# senseBox-BMP280_v20.net
KiCad netlist of a schematic drawn in EAGLE
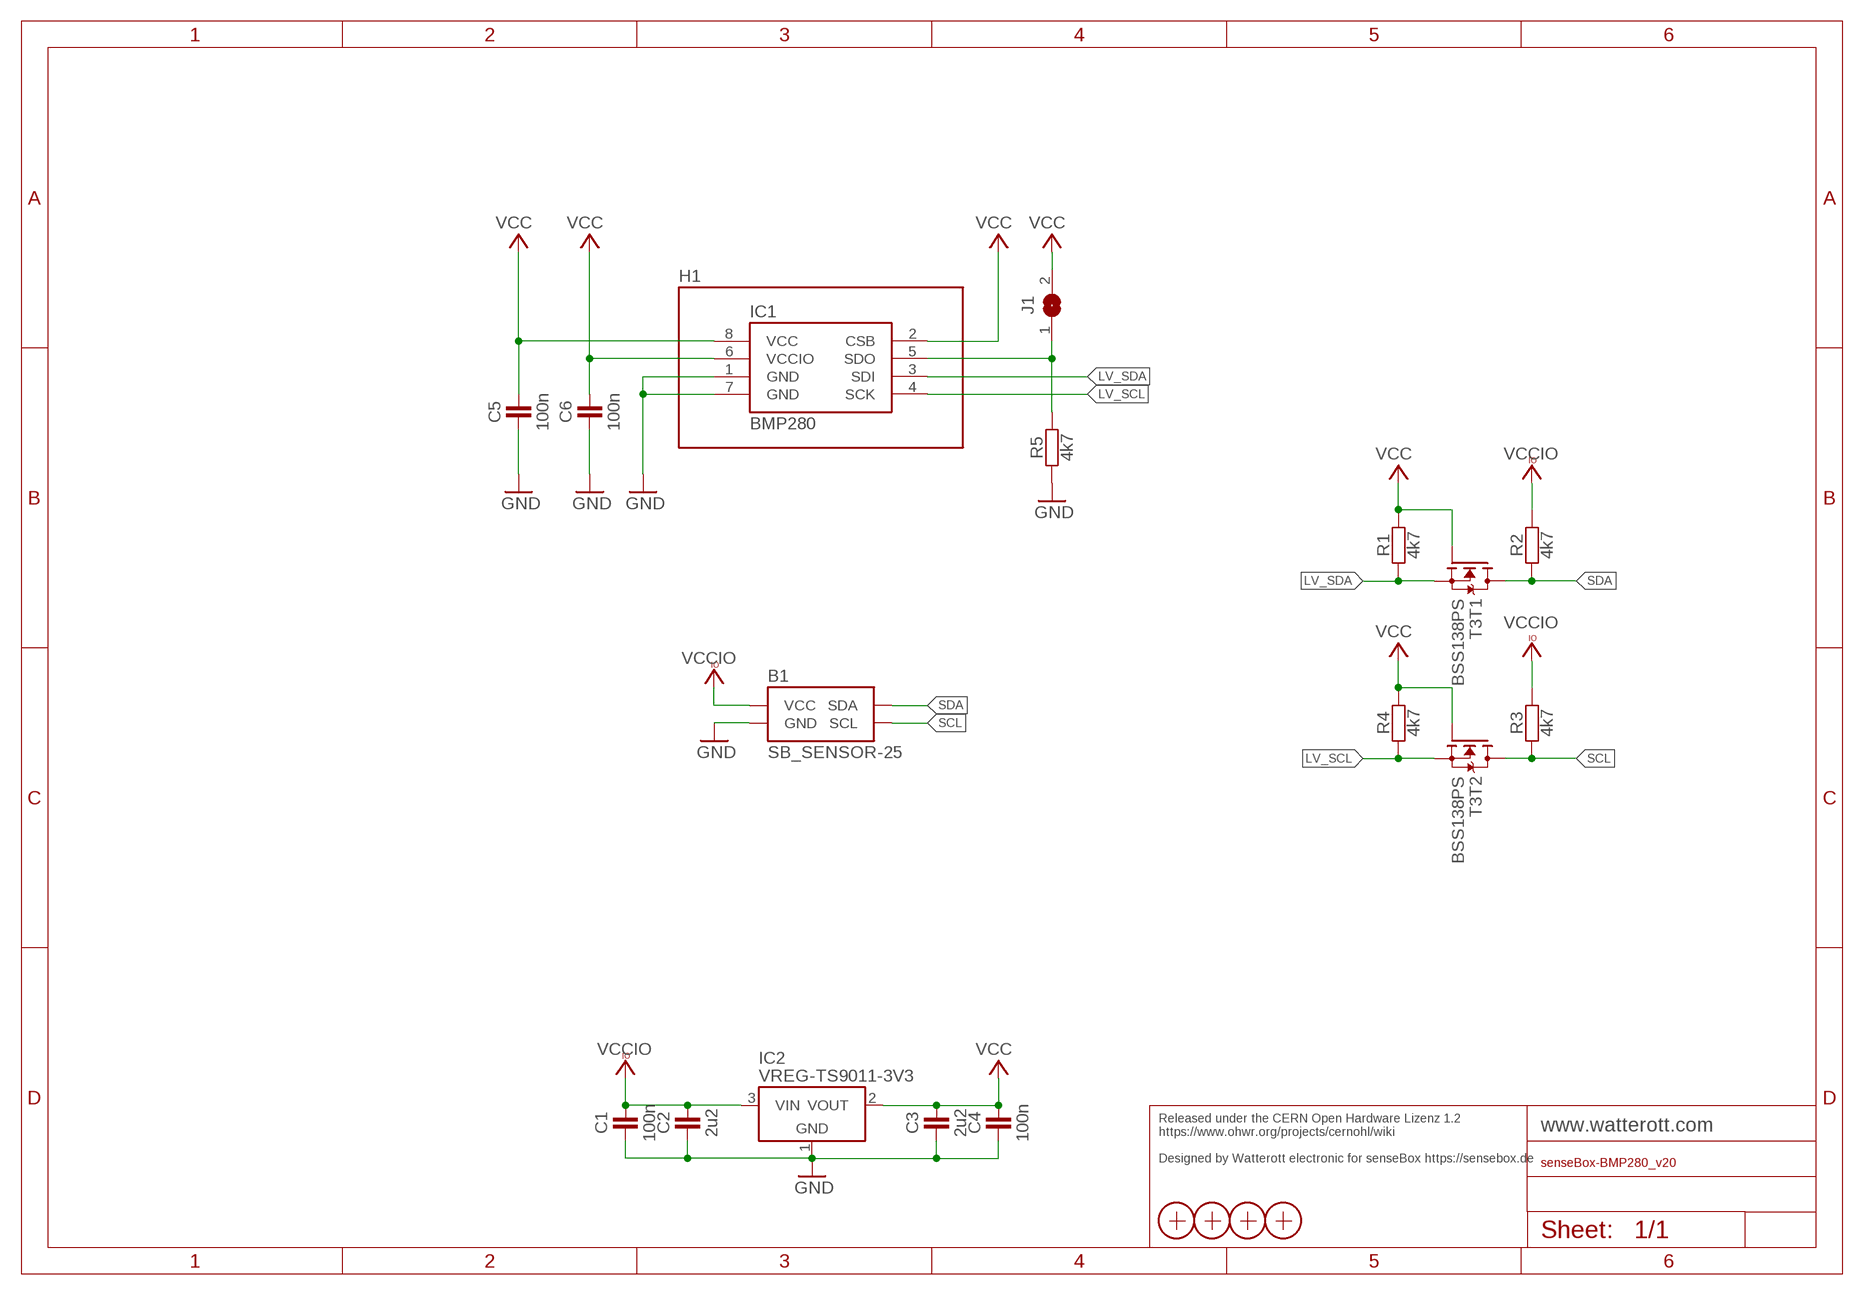
[diagram p0: schematic, sheet 1]

(export (version "E")
  (design (tool "Eeschema 10.0.6"))
  (components
    (comp (ref "B1")
      (value "SB_SENSOR-25")
      (footprint "eagle-import:SB-25X25")
      (libsource (lib "eagle-import") (part "SB_SENSOR-25"))
    )
    (comp (ref "C1")
      (value "100n")
      (footprint "eagle-import:C0402")
      (libsource (lib "eagle-import") (part "CAPACITOR-0402"))
    )
    (comp (ref "C2")
      (value "2u2")
      (footprint "eagle-import:C0402")
      (libsource (lib "eagle-import") (part "CAPACITOR-0402"))
    )
    (comp (ref "C3")
      (value "2u2")
      (footprint "eagle-import:C0402")
      (libsource (lib "eagle-import") (part "CAPACITOR-0402"))
    )
    (comp (ref "C4")
      (value "100n")
      (footprint "eagle-import:C0402")
      (libsource (lib "eagle-import") (part "CAPACITOR-0402"))
    )
    (comp (ref "C5")
      (value "100n")
      (footprint "eagle-import:C0402")
      (libsource (lib "eagle-import") (part "CAPACITOR-0402"))
    )
    (comp (ref "C6")
      (value "100n")
      (footprint "eagle-import:C0402")
      (libsource (lib "eagle-import") (part "CAPACITOR-0402"))
    )
    (comp (ref "H1")
      (value "SF2")
      (footprint "eagle-import:SF2")
      (libsource (lib "eagle-import") (part "SF2"))
    )
    (comp (ref "IC1")
      (value "BMP280")
      (footprint "eagle-import:LGA8")
      (libsource (lib "eagle-import") (part "BMP280"))
    )
    (comp (ref "IC2")
      (value "VREG-TS9011-3V3")
      (footprint "eagle-import:SOT23")
      (libsource (lib "eagle-import") (part "VREG-TS9011-3V3"))
    )
    (comp (ref "J1")
      (value "JUMPER2-0402-NC")
      (footprint "eagle-import:JUMPER2-0402_NC")
      (libsource (lib "eagle-import") (part "JUMPER2-0402-NC"))
    )
    (comp (ref "R1")
      (value "4k7")
      (footprint "eagle-import:C0402")
      (libsource (lib "eagle-import") (part "RESISTOR-0402"))
    )
    (comp (ref "R2")
      (value "4k7")
      (footprint "eagle-import:C0402")
      (libsource (lib "eagle-import") (part "RESISTOR-0402"))
    )
    (comp (ref "R3")
      (value "4k7")
      (footprint "eagle-import:C0402")
      (libsource (lib "eagle-import") (part "RESISTOR-0402"))
    )
    (comp (ref "R4")
      (value "4k7")
      (footprint "eagle-import:C0402")
      (libsource (lib "eagle-import") (part "RESISTOR-0402"))
    )
    (comp (ref "R5")
      (value "4k7")
      (footprint "eagle-import:C0402")
      (libsource (lib "eagle-import") (part "RESISTOR-0402"))
    )
    (comp (ref "T3")
      (value "BSS138PS")
      (footprint "eagle-import:SOT363")
      (libsource (lib "eagle-import") (part "BSS138PS"))
    )
    (comp (ref "X1")
      (value "PASSER-07")
      (footprint "eagle-import:PASSER_07MM")
      (libsource (lib "eagle-import") (part "PASSER-07"))
    )
    (comp (ref "X2")
      (value "PASSER-07")
      (footprint "eagle-import:PASSER_07MM")
      (libsource (lib "eagle-import") (part "PASSER-07"))
    )
    (comp (ref "X3")
      (value "PASSER-07")
      (footprint "eagle-import:PASSER_07MM")
      (libsource (lib "eagle-import") (part "PASSER-07"))
    )
    (comp (ref "X4")
      (value "PASSER-07")
      (footprint "eagle-import:PASSER_07MM")
      (libsource (lib "eagle-import") (part "PASSER-07"))
    )
  )
  (nets
    (net (code "1") (name "GND") (class "Default")
      (node (ref "B1") (pin "GND") (pinfunction "GND_GND") (pintype "power_in"))
      (node (ref "C1") (pin "1") (pinfunction "1_1") (pintype "passive"))
      (node (ref "C2") (pin "1") (pinfunction "1_1") (pintype "passive"))
      (node (ref "C3") (pin "1") (pinfunction "1_1") (pintype "passive"))
      (node (ref "C4") (pin "1") (pinfunction "1_1") (pintype "passive"))
      (node (ref "C5") (pin "1") (pinfunction "1_1") (pintype "passive"))
      (node (ref "C6") (pin "1") (pinfunction "1_1") (pintype "passive"))
      (node (ref "IC1") (pin "1") (pinfunction "GND_1") (pintype "power_in"))
      (node (ref "IC1") (pin "7") (pinfunction "GND_7") (pintype "power_in"))
      (node (ref "IC2") (pin "1") (pinfunction "GND_1") (pintype "power_in"))
      (node (ref "R5") (pin "1") (pinfunction "1_1") (pintype "passive"))
    )
    (net (code "2") (name "LV_SCL") (class "Default")
      (node (ref "IC1") (pin "4") (pinfunction "SCK_4") (pintype "bidirectional"))
      (node (ref "R4") (pin "1") (pinfunction "1_1") (pintype "passive"))
      (node (ref "T3") (pin "4") (pinfunction "S_4") (pintype "passive"))
    )
    (net (code "3") (name "LV_SDA") (class "Default")
      (node (ref "IC1") (pin "3") (pinfunction "SDI_3") (pintype "bidirectional"))
      (node (ref "R1") (pin "1") (pinfunction "1_1") (pintype "passive"))
      (node (ref "T3") (pin "1") (pinfunction "S_1") (pintype "passive"))
    )
    (net (code "4") (name "Net-(IC1-SDO)") (class "Default")
      (node (ref "IC1") (pin "5") (pinfunction "SDO_5") (pintype "bidirectional"))
      (node (ref "J1") (pin "1") (pinfunction "1_1") (pintype "passive"))
      (node (ref "R5") (pin "2") (pinfunction "2_2") (pintype "passive"))
    )
    (net (code "5") (name "SCL") (class "Default")
      (node (ref "B1") (pin "SCL") (pinfunction "SCL_SCL") (pintype "bidirectional"))
      (node (ref "R3") (pin "1") (pinfunction "1_1") (pintype "passive"))
      (node (ref "T3") (pin "3") (pinfunction "D_3") (pintype "passive"))
    )
    (net (code "6") (name "SDA") (class "Default")
      (node (ref "B1") (pin "SDA") (pinfunction "SDA_SDA") (pintype "bidirectional"))
      (node (ref "R2") (pin "1") (pinfunction "1_1") (pintype "passive"))
      (node (ref "T3") (pin "6") (pinfunction "D_6") (pintype "passive"))
    )
    (net (code "7") (name "VCC") (class "Default")
      (node (ref "C3") (pin "2") (pinfunction "2_2") (pintype "passive"))
      (node (ref "C4") (pin "2") (pinfunction "2_2") (pintype "passive"))
      (node (ref "C5") (pin "2") (pinfunction "2_2") (pintype "passive"))
      (node (ref "C6") (pin "2") (pinfunction "2_2") (pintype "passive"))
      (node (ref "IC1") (pin "2") (pinfunction "CSB_2") (pintype "input"))
      (node (ref "IC1") (pin "6") (pinfunction "VCCIO_6") (pintype "power_in"))
      (node (ref "IC1") (pin "8") (pinfunction "VCC_8") (pintype "power_in"))
      (node (ref "IC2") (pin "2") (pinfunction "VOUT_2") (pintype "power_in"))
      (node (ref "J1") (pin "2") (pinfunction "2_2") (pintype "passive"))
      (node (ref "R1") (pin "2") (pinfunction "2_2") (pintype "passive"))
      (node (ref "R4") (pin "2") (pinfunction "2_2") (pintype "passive"))
      (node (ref "T3") (pin "2") (pinfunction "G_2") (pintype "passive"))
      (node (ref "T3") (pin "5") (pinfunction "G_5") (pintype "passive"))
    )
    (net (code "8") (name "VCCIO") (class "Default")
      (node (ref "B1") (pin "VCC") (pinfunction "VCC_VCC") (pintype "power_in"))
      (node (ref "C1") (pin "2") (pinfunction "2_2") (pintype "passive"))
      (node (ref "C2") (pin "2") (pinfunction "2_2") (pintype "passive"))
      (node (ref "IC2") (pin "3") (pinfunction "VIN_3") (pintype "power_in"))
      (node (ref "R2") (pin "2") (pinfunction "2_2") (pintype "passive"))
      (node (ref "R3") (pin "2") (pinfunction "2_2") (pintype "passive"))
    )
  )
)
